# Ampli_audio.net
KiCad netlist of a schematic drawn in Altium Designer
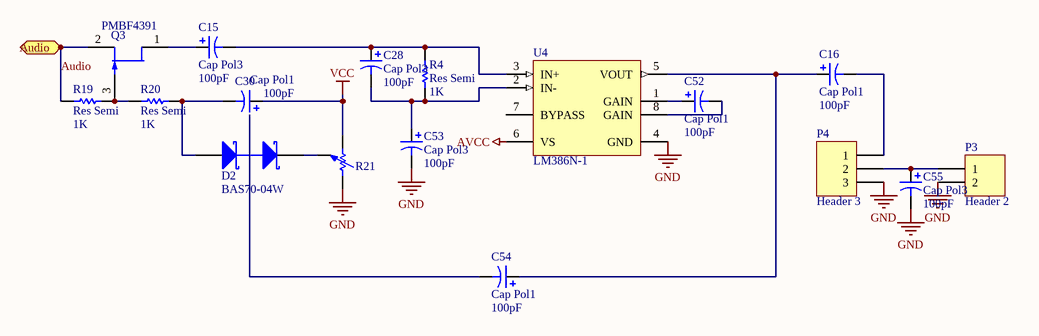
[diagram p0: Ampli_audio.SchDoc]

(export (version "E")
  (design (tool "Eeschema 10.0.6"))
  (components
    (comp (ref "C15")
      (value "Cap Pol3")
      (footprint "C0805")
      (description "Polarized Capacitor (Surface Mount)")
      (fields (field (name "ALTIUM_VALUE") "100pF") (field (name "PUBLISHER") "Altium Limited"))
      (libsource (lib "Miscellaneous Devices") (part "Cap Pol3"))
    )
    (comp (ref "C16")
      (value "Cap Pol1")
      (footprint "B")
      (description "Polarized Capacitor (Radial)")
      (fields (field (name "ALTIUM_VALUE") "100pF") (field (name "PUBLISHER") "Altium Limited"))
      (libsource (lib "Miscellaneous Devices") (part "Cap Pol1"))
    )
    (comp (ref "C28")
      (value "Cap Pol3")
      (footprint "C0805")
      (description "Polarized Capacitor (Surface Mount)")
      (fields (field (name "ALTIUM_VALUE") "100pF") (field (name "PUBLISHER") "Altium Limited"))
      (libsource (lib "Miscellaneous Devices") (part "Cap Pol3"))
    )
    (comp (ref "C30")
      (value "Cap Pol1")
      (footprint "B")
      (description "Polarized Capacitor (Radial)")
      (fields (field (name "ALTIUM_VALUE") "100pF") (field (name "PUBLISHER") "Altium Limited"))
      (libsource (lib "Miscellaneous Devices") (part "Cap Pol1"))
    )
    (comp (ref "C52")
      (value "Cap Pol1")
      (footprint "B")
      (description "Polarized Capacitor (Radial)")
      (fields (field (name "ALTIUM_VALUE") "100pF") (field (name "PUBLISHER") "Altium Limited"))
      (libsource (lib "Miscellaneous Devices") (part "Cap Pol1"))
    )
    (comp (ref "C53")
      (value "Cap Pol3")
      (footprint "C0805")
      (description "Polarized Capacitor (Surface Mount)")
      (fields (field (name "ALTIUM_VALUE") "100pF") (field (name "PUBLISHER") "Altium Limited"))
      (libsource (lib "Miscellaneous Devices") (part "Cap Pol3"))
    )
    (comp (ref "C54")
      (value "Cap Pol1")
      (footprint "B")
      (description "Polarized Capacitor (Radial)")
      (fields (field (name "ALTIUM_VALUE") "100pF") (field (name "PUBLISHER") "Altium Limited"))
      (libsource (lib "Miscellaneous Devices") (part "Cap Pol1"))
    )
    (comp (ref "C55")
      (value "Cap Pol3")
      (footprint "C0805")
      (description "Polarized Capacitor (Surface Mount)")
      (fields (field (name "ALTIUM_VALUE") "100pF") (field (name "PUBLISHER") "Altium Limited"))
      (libsource (lib "Miscellaneous Devices") (part "Cap Pol3"))
    )
    (comp (ref "D2")
      (value "BAS70-04W")
      (footprint "SOT323_N")
      (description "Schottky Barrier Double Diode")
      (fields (field (name "PUBLISHER") "Altium Limited"))
      (libsource (lib "Philips Discrete Diode - Schottky") (part "BAS70-04W"))
    )
    (comp (ref "P3")
      (value "Header 2")
      (footprint "HDR1X2")
      (description "Header, 2-Pin")
      (fields (field (name "PUBLISHER") "Altium Limited"))
      (libsource (lib "Miscellaneous Connectors") (part "Header 2"))
    )
    (comp (ref "P4")
      (value "Header 3")
      (footprint "HDR1X3")
      (description "Header, 3-Pin")
      (fields (field (name "PUBLISHER") "Altium Limited"))
      (libsource (lib "Miscellaneous Connectors") (part "Header 3"))
    )
    (comp (ref "Q3")
      (value "PMBF4391")
      (footprint "SOT23_N")
      (description "N-channel Silicon Junction Field-effect Transistor")
      (fields (field (name "PUBLISHER") "Altium Limited"))
      (libsource (lib "Philips Discrete JFET") (part "PMBF4391"))
    )
    (comp (ref "R4")
      (value "Res Semi")
      (footprint "2012[0805]")
      (description "Semiconductor Resistor")
      (fields (field (name "ALTIUM_VALUE") "1K") (field (name "PUBLISHER") "Altium Limited"))
      (libsource (lib "Miscellaneous Devices") (part "Res Semi"))
    )
    (comp (ref "R19")
      (value "Res Semi")
      (footprint "2012[0805]")
      (description "Semiconductor Resistor")
      (fields (field (name "ALTIUM_VALUE") "1K") (field (name "PUBLISHER") "Altium Limited"))
      (libsource (lib "Miscellaneous Devices") (part "Res Semi"))
    )
    (comp (ref "R20")
      (value "Res Semi")
      (footprint "2012[0805]")
      (description "Semiconductor Resistor")
      (fields (field (name "ALTIUM_VALUE") "1K") (field (name "PUBLISHER") "Altium Limited"))
      (libsource (lib "Miscellaneous Devices") (part "Res Semi"))
    )
    (comp (ref "R21") (value "Pot") (footprint "Potenciometro") (libsource (lib "epf") (part "Pot")))
    (comp (ref "U4")
      (value "LM386N-1")
      (footprint "N08E")
      (description "Low Voltage Audio Power Amplifier")
      (fields
        (field (name "MANUFACTURER") "National Semiconductor")
        (field (name "DIGIKEYPARTNUMBER") "LM386N-1-ND")
      )
      (libsource (lib "NSC Audio") (part "LM386N-1"))
    )
  )
  (nets
    (net (code "1") (name "/Audio") (class "Default")
      (node (ref "Q3") (pin "2") (pinfunction "S_2") (pintype "passive"))
      (node (ref "R19") (pin "1") (pinfunction "1_1") (pintype "passive"))
    )
    (net (code "2") (name "AVCC") (class "Default")
      (node (ref "U4") (pin "6") (pinfunction "VS_6") (pintype "power_in"))
    )
    (net (code "3") (name "GND") (class "Default")
      (node (ref "C53") (pin "2") (pinfunction "2_2") (pintype "passive"))
      (node (ref "C55") (pin "2") (pinfunction "2_2") (pintype "passive"))
      (node (ref "P3") (pin "2") (pinfunction "2_2") (pintype "passive"))
      (node (ref "P4") (pin "3") (pinfunction "3_3") (pintype "passive"))
      (node (ref "R21") (pin "1") (pinfunction "1_1") (pintype "passive"))
      (node (ref "U4") (pin "4") (pinfunction "GND_4") (pintype "power_in"))
    )
    (net (code "4") (name "Net-(C16-Pad2)") (class "Default")
      (node (ref "C16") (pin "2") (pinfunction "2_2") (pintype "passive"))
      (node (ref "P4") (pin "1") (pinfunction "1_1") (pintype "passive"))
    )
    (net (code "5") (name "Net-(C52-Pad1)") (class "Default")
      (node (ref "C52") (pin "1") (pinfunction "1_1") (pintype "passive"))
      (node (ref "U4") (pin "1") (pinfunction "GAIN_1") (pintype "passive"))
    )
    (net (code "6") (name "Net-(C52-Pad2)") (class "Default")
      (node (ref "C52") (pin "2") (pinfunction "2_2") (pintype "passive"))
      (node (ref "U4") (pin "8") (pinfunction "GAIN_8") (pintype "passive"))
    )
    (net (code "7") (name "Net-(C55-Pad1)") (class "Default")
      (node (ref "C55") (pin "1") (pinfunction "1_1") (pintype "passive"))
      (node (ref "P3") (pin "1") (pinfunction "1_1") (pintype "passive"))
      (node (ref "P4") (pin "2") (pinfunction "2_2") (pintype "passive"))
    )
    (net (code "8") (name "Net-(D2-A)") (class "Default")
      (node (ref "C30") (pin "2") (pinfunction "2_2") (pintype "passive"))
      (node (ref "D2") (pin "1") (pinfunction "A_1") (pintype "passive"))
      (node (ref "R20") (pin "2") (pinfunction "2_2") (pintype "passive"))
    )
    (net (code "9") (name "Net-(D2-C)") (class "Default")
      (node (ref "C54") (pin "2") (pinfunction "2_2") (pintype "passive"))
      (node (ref "D2") (pin "3") (pinfunction "C_3") (pintype "passive"))
    )
    (net (code "10") (name "Net-(D2-K)") (class "Default")
      (node (ref "D2") (pin "2") (pinfunction "K_2") (pintype "passive"))
      (node (ref "R21") (pin "3") (pinfunction "3_3") (pintype "passive"))
    )
    (net (code "11") (name "Net-(Q3-D)") (class "Default")
      (node (ref "C15") (pin "1") (pinfunction "1_1") (pintype "passive"))
      (node (ref "Q3") (pin "1") (pinfunction "D_1") (pintype "passive"))
    )
    (net (code "12") (name "Net-(Q3-G)") (class "Default")
      (node (ref "Q3") (pin "3") (pinfunction "G_3") (pintype "passive"))
      (node (ref "R19") (pin "2") (pinfunction "2_2") (pintype "passive"))
      (node (ref "R20") (pin "1") (pinfunction "1_1") (pintype "passive"))
    )
    (net (code "13") (name "Net-(U4-IN+)") (class "Default")
      (node (ref "C15") (pin "2") (pinfunction "2_2") (pintype "passive"))
      (node (ref "C28") (pin "1") (pinfunction "1_1") (pintype "passive"))
      (node (ref "R4") (pin "2") (pinfunction "2_2") (pintype "passive"))
      (node (ref "U4") (pin "3") (pinfunction "IN+_3") (pintype "input"))
    )
    (net (code "14") (name "Net-(U4-IN-)") (class "Default")
      (node (ref "C28") (pin "2") (pinfunction "2_2") (pintype "passive"))
      (node (ref "C53") (pin "1") (pinfunction "1_1") (pintype "passive"))
      (node (ref "R4") (pin "1") (pinfunction "1_1") (pintype "passive"))
      (node (ref "U4") (pin "2") (pinfunction "IN-_2") (pintype "input"))
    )
    (net (code "15") (name "Net-(U4-VOUT)") (class "Default")
      (node (ref "C16") (pin "1") (pinfunction "1_1") (pintype "passive"))
      (node (ref "C54") (pin "1") (pinfunction "1_1") (pintype "passive"))
      (node (ref "U4") (pin "5") (pinfunction "VOUT_5") (pintype "output"))
    )
    (net (code "16") (name "VCC") (class "Default")
      (node (ref "C30") (pin "1") (pinfunction "1_1") (pintype "passive"))
      (node (ref "R21") (pin "2") (pinfunction "2_2") (pintype "passive"))
    )
    (net (code "17") (name "unconnected-(U4-BYPASS-Pad7)") (class "Default")
      (node (ref "U4") (pin "7") (pinfunction "BYPASS_7") (pintype "passive"))
    )
  )
)
